# 13-USB_HS.net
KiCad netlist of a schematic drawn in Altium Designer
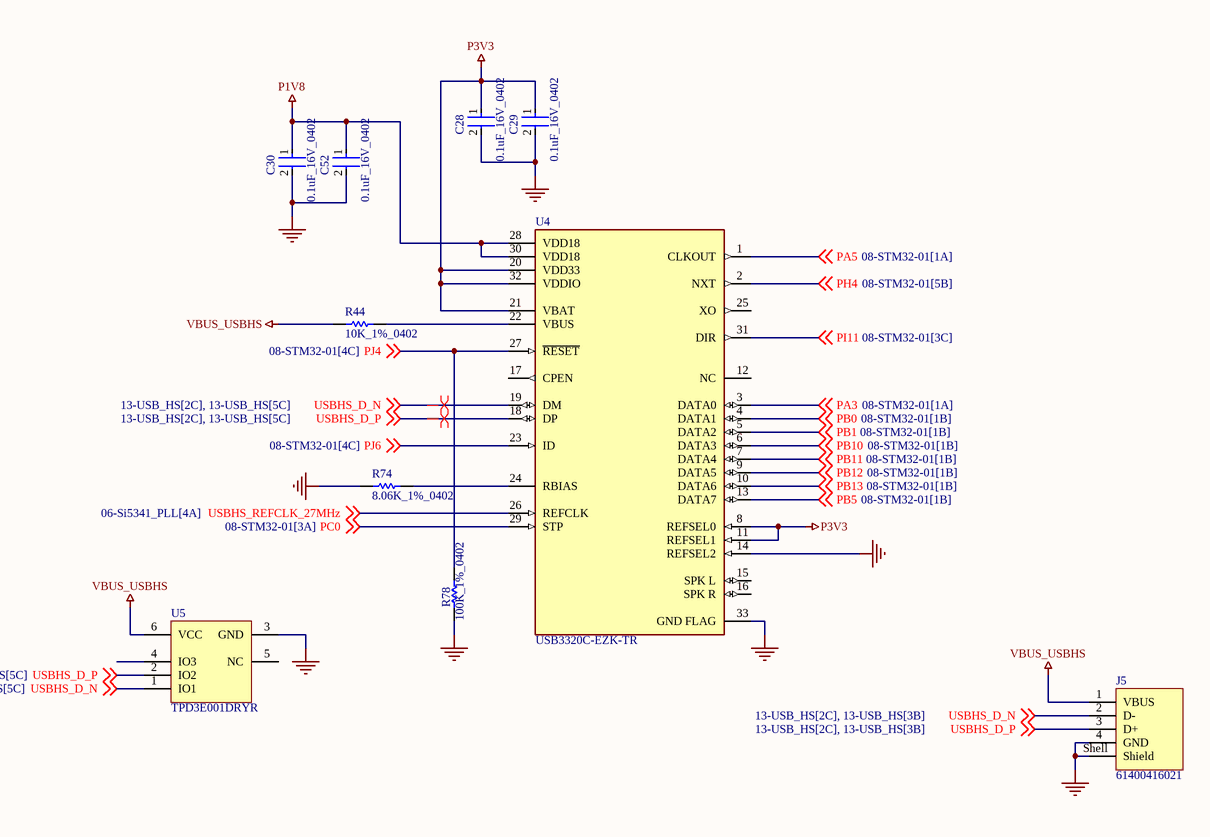
[diagram p0: 13-USB_HS.SchDoc]

(export (version "E")
  (design (tool "Eeschema 10.0.6"))
  (components
    (comp (ref "C28")
      (value "0.1uF_16V_0402")
      (footprint "FP-C0402-BB-MFG")
      (description "CAP CER 0.1UF 16V 5% X7R 0402")
      (fields
        (field (name "MANUFACTURER") "Kemet")
        (field (name "MANUFACTURER PART NUMBER") "C0402C104J4RACTU")
      )
      (libsource (lib "Altium Content Vault") (part "b4654b650e69147ec39a6b967a45e02"))
    )
    (comp (ref "C29")
      (value "0.1uF_16V_0402")
      (footprint "FP-C0402-BB-MFG")
      (description "CAP CER 0.1UF 16V 5% X7R 0402")
      (fields
        (field (name "MANUFACTURER") "Kemet")
        (field (name "MANUFACTURER PART NUMBER") "C0402C104J4RACTU")
      )
      (libsource (lib "Altium Content Vault") (part "b4654b650e69147ec39a6b967a45e02"))
    )
    (comp (ref "C30")
      (value "0.1uF_16V_0402")
      (footprint "FP-C0402-BB-MFG")
      (description "CAP CER 0.1UF 16V 5% X7R 0402")
      (fields
        (field (name "MANUFACTURER") "Kemet")
        (field (name "MANUFACTURER PART NUMBER") "C0402C104J4RACTU")
      )
      (libsource (lib "Altium Content Vault") (part "b4654b650e69147ec39a6b967a45e02"))
    )
    (comp (ref "C52")
      (value "0.1uF_16V_0402")
      (footprint "FP-C0402-BB-MFG")
      (description "CAP CER 0.1UF 16V 5% X7R 0402")
      (fields
        (field (name "MANUFACTURER") "Kemet")
        (field (name "MANUFACTURER PART NUMBER") "C0402C104J4RACTU")
      )
      (libsource (lib "Altium Content Vault") (part "b4654b650e69147ec39a6b967a45e02"))
    )
    (comp (ref "J5")
      (value "61400416021")
      (footprint "61400416021")
      (libsource (lib "Altium Content Vault") (part "USB 2.0_Type A_Receptacle_1 Port"))
    )
    (comp (ref "R44")
      (value "10K_1%_0402")
      (footprint "RESC1005X40X25NL10T10")
      (fields (field (name "MANUFACTURER") "Bourns") (field (name "PART NUMBER") "CR0402-FX-1002GLF"))
      (libsource (lib "Altium Content Vault") (part "RES"))
    )
    (comp (ref "R74")
      (value "8.06K_1%_0402")
      (footprint "RESC1005X40X25LL05T05")
      (fields (field (name "MANUFACTURER") "Panasonic") (field (name "PART NUMBER") "ERJ-2RKF8061X"))
      (libsource (lib "Altium Content Vault") (part "RES"))
    )
    (comp (ref "R78")
      (value "100K_1%_0402")
      (footprint "RESC1005X40X25ML05T10")
      (fields (field (name "MANUFACTURER") "Yageo") (field (name "PART NUMBER") "RC0402FR-13100KL"))
      (libsource (lib "Altium Content Vault") (part "RES"))
    )
    (comp (ref "U4")
      (value "USB3320C-EZK-TR")
      (footprint "FP-32QFN-3304-5X5B-MFG")
      (description "IC TRANSCEIVER HALF 1/1 32QFN")
      (fields
        (field (name "MANUFACTURER") "Microchip")
        (field (name "OCTOPART") "https://octopart.com/usb3320c-ezk-tr-microchip-24995468")
      )
      (libsource (lib "Altium Content Vault") (part "d497a40fedd2315480c30a8e5861190"))
    )
    (comp (ref "U5")
      (value "TPD3E001DRYR")
      (footprint "DRY0006A")
      (fields (field (name "MANUFACTURER") "Texas Instruments"))
      (libsource (lib "Altium Content Vault") (part "TI-TPD3E001-SON_DRY-6"))
    )
  )
  (nets
    (net (code "1") (name "GND") (class "Default")
      (node (ref "C28") (pin "2") (pinfunction "2_2") (pintype "passive"))
      (node (ref "C29") (pin "2") (pinfunction "2_2") (pintype "passive"))
      (node (ref "C30") (pin "2") (pinfunction "2_2") (pintype "passive"))
      (node (ref "C52") (pin "2") (pinfunction "2_2") (pintype "passive"))
      (node (ref "J5") (pin "4") (pinfunction "GND_4") (pintype "passive"))
      (node (ref "J5") (pin "Shell") (pinfunction "Shield_Shell") (pintype "passive"))
      (node (ref "R74") (pin "1") (pinfunction "1_1") (pintype "passive"))
      (node (ref "R78") (pin "1") (pinfunction "1_1") (pintype "passive"))
      (node (ref "U4") (pin "14") (pinfunction "REFSEL2_14") (pintype "input"))
      (node (ref "U4") (pin "33") (pinfunction "GND_FLAG_33") (pintype "power_in"))
      (node (ref "U5") (pin "3") (pinfunction "GND_3") (pintype "power_in"))
    )
    (net (code "2") (name "Net-(U4-RBIAS)") (class "Default")
      (node (ref "R74") (pin "2") (pinfunction "2_2") (pintype "passive"))
      (node (ref "U4") (pin "24") (pinfunction "RBIAS_24") (pintype "power_in"))
    )
    (net (code "3") (name "Net-(U4-VBUS)") (class "Default")
      (node (ref "R44") (pin "1") (pinfunction "1_1") (pintype "passive"))
      (node (ref "U4") (pin "22") (pinfunction "VBUS_22") (pintype "power_in"))
    )
    (net (code "4") (name "P1V8") (class "Default")
      (node (ref "C30") (pin "1") (pinfunction "1_1") (pintype "passive"))
      (node (ref "C52") (pin "1") (pinfunction "1_1") (pintype "passive"))
      (node (ref "U4") (pin "28") (pinfunction "VDD18_28") (pintype "power_in"))
      (node (ref "U4") (pin "30") (pinfunction "VDD18_30") (pintype "power_in"))
    )
    (net (code "5") (name "P3V3") (class "Default")
      (node (ref "C28") (pin "1") (pinfunction "1_1") (pintype "passive"))
      (node (ref "C29") (pin "1") (pinfunction "1_1") (pintype "passive"))
      (node (ref "U4") (pin "11") (pinfunction "REFSEL1_11") (pintype "input"))
      (node (ref "U4") (pin "20") (pinfunction "VDD33_20") (pintype "power_in"))
      (node (ref "U4") (pin "21") (pinfunction "VBAT_21") (pintype "power_in"))
      (node (ref "U4") (pin "32") (pinfunction "VDDIO_32") (pintype "power_in"))
      (node (ref "U4") (pin "8") (pinfunction "REFSEL0_8") (pintype "input"))
    )
    (net (code "6") (name "PA3") (class "Default")
      (node (ref "U4") (pin "3") (pinfunction "DATA0_3") (pintype "bidirectional"))
    )
    (net (code "7") (name "PA5") (class "Default")
      (node (ref "U4") (pin "1") (pinfunction "CLKOUT_1") (pintype "output"))
    )
    (net (code "8") (name "PB0") (class "Default")
      (node (ref "U4") (pin "4") (pinfunction "DATA1_4") (pintype "bidirectional"))
    )
    (net (code "9") (name "PB1") (class "Default")
      (node (ref "U4") (pin "5") (pinfunction "DATA2_5") (pintype "bidirectional"))
    )
    (net (code "10") (name "PB5") (class "Default")
      (node (ref "U4") (pin "13") (pinfunction "DATA7_13") (pintype "bidirectional"))
    )
    (net (code "11") (name "PB10") (class "Default")
      (node (ref "U4") (pin "6") (pinfunction "DATA3_6") (pintype "bidirectional"))
    )
    (net (code "12") (name "PB11") (class "Default")
      (node (ref "U4") (pin "7") (pinfunction "DATA4_7") (pintype "bidirectional"))
    )
    (net (code "13") (name "PB12") (class "Default")
      (node (ref "U4") (pin "9") (pinfunction "DATA5_9") (pintype "bidirectional"))
    )
    (net (code "14") (name "PB13") (class "Default")
      (node (ref "U4") (pin "10") (pinfunction "DATA6_10") (pintype "bidirectional"))
    )
    (net (code "15") (name "PC0") (class "Default")
      (node (ref "U4") (pin "29") (pinfunction "STP_29") (pintype "input"))
    )
    (net (code "16") (name "PH4") (class "Default")
      (node (ref "U4") (pin "2") (pinfunction "NXT_2") (pintype "output"))
    )
    (net (code "17") (name "PI11") (class "Default")
      (node (ref "U4") (pin "31") (pinfunction "DIR_31") (pintype "output"))
    )
    (net (code "18") (name "PJ4") (class "Default")
      (node (ref "R78") (pin "2") (pinfunction "2_2") (pintype "passive"))
      (node (ref "U4") (pin "27") (pinfunction "~{RESET}_27") (pintype "input"))
    )
    (net (code "19") (name "PJ6") (class "Default")
      (node (ref "U4") (pin "23") (pinfunction "ID_23") (pintype "input"))
    )
    (net (code "20") (name "USBHS_D_N") (class "Default")
      (node (ref "J5") (pin "2") (pinfunction "D-_2") (pintype "passive"))
      (node (ref "U4") (pin "19") (pinfunction "DM_19") (pintype "bidirectional"))
      (node (ref "U5") (pin "1") (pinfunction "IO1_1") (pintype "passive"))
    )
    (net (code "21") (name "USBHS_D_P") (class "Default")
      (node (ref "J5") (pin "3") (pinfunction "D+_3") (pintype "passive"))
      (node (ref "U4") (pin "18") (pinfunction "DP_18") (pintype "bidirectional"))
      (node (ref "U5") (pin "2") (pinfunction "IO2_2") (pintype "passive"))
    )
    (net (code "22") (name "USBHS_REFCLK_27MHz") (class "Default")
      (node (ref "U4") (pin "26") (pinfunction "REFCLK_26") (pintype "input"))
    )
    (net (code "23") (name "VBUS_USBHS") (class "Default")
      (node (ref "J5") (pin "1") (pinfunction "VBUS_1") (pintype "passive"))
      (node (ref "R44") (pin "2") (pinfunction "2_2") (pintype "passive"))
      (node (ref "U5") (pin "6") (pinfunction "VCC_6") (pintype "power_in"))
    )
    (net (code "24") (name "unconnected-(U4-CPEN-Pad17)") (class "Default")
      (node (ref "U4") (pin "17") (pinfunction "CPEN_17") (pintype "output"))
    )
    (net (code "25") (name "unconnected-(U4-NC-Pad12)") (class "Default")
      (node (ref "U4") (pin "12") (pinfunction "NC_12") (pintype "passive"))
    )
    (net (code "26") (name "unconnected-(U4-SPK_L-Pad15)") (class "Default")
      (node (ref "U4") (pin "15") (pinfunction "SPK_L_15") (pintype "bidirectional"))
    )
    (net (code "27") (name "unconnected-(U4-SPK_R-Pad16)") (class "Default")
      (node (ref "U4") (pin "16") (pinfunction "SPK_R_16") (pintype "bidirectional"))
    )
    (net (code "28") (name "unconnected-(U4-XO-Pad25)") (class "Default")
      (node (ref "U4") (pin "25") (pinfunction "XO_25") (pintype "output"))
    )
    (net (code "29") (name "unconnected-(U5-IO3-Pad4)") (class "Default")
      (node (ref "U5") (pin "4") (pinfunction "IO3_4") (pintype "passive"))
    )
    (net (code "30") (name "unconnected-(U5-NC-Pad5)") (class "Default")
      (node (ref "U5") (pin "5") (pinfunction "NC_5") (pintype "passive"))
    )
  )
)
